# battery_current_sensor.net
KiCad netlist of a schematic drawn in Altium Designer
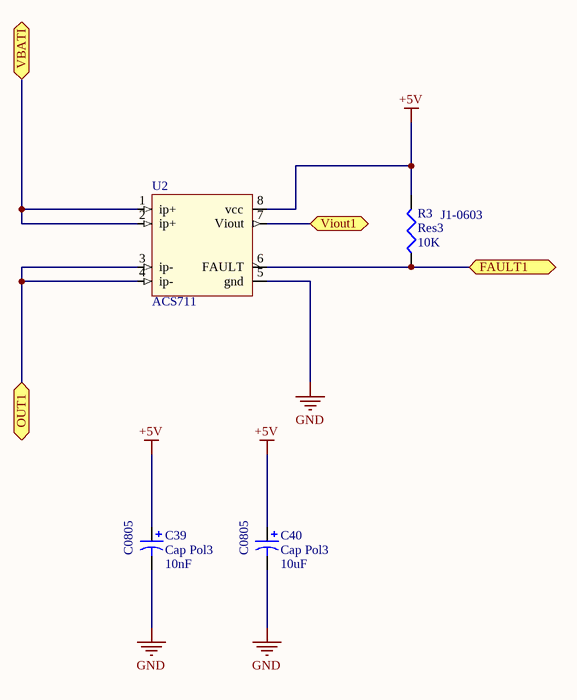
[diagram p0: battery current sensor.SchDoc]

(export (version "E")
  (design (tool "Eeschema 10.0.6"))
  (components
    (comp (ref "C39")
      (value "Cap Pol3")
      (footprint "C0805")
      (description "Polarized Capacitor (Surface Mount)")
      (fields
        (field (name "PACKAGEREFERENCE") "C0805")
        (field (name "ALTIUM_VALUE") "10nF")
        (field (name "PUBLISHER") "Altium Limited")
      )
      (libsource (lib "Miscellaneous Devices") (part "Cap Pol3"))
    )
    (comp (ref "C40")
      (value "Cap Pol3")
      (footprint "C0805")
      (description "Polarized Capacitor (Surface Mount)")
      (fields
        (field (name "PACKAGEREFERENCE") "C0805")
        (field (name "ALTIUM_VALUE") "10uF")
        (field (name "PUBLISHER") "Altium Limited")
      )
      (libsource (lib "Miscellaneous Devices") (part "Cap Pol3"))
    )
    (comp (ref "R3")
      (value "Res3")
      (footprint "J1-0603")
      (description "Resistor")
      (fields
        (field (name "PACKAGEREFERENCE") "J1-0603")
        (field (name "ALTIUM_VALUE") "10K")
        (field (name "PUBLISHER") "Altium Limited")
      )
      (libsource (lib "Miscellaneous Devices") (part "Res3"))
    )
    (comp (ref "U2") (value "ACS711") (footprint "ACS711") (libsource (lib "ACS711") (part "ACS711")))
  )
  (nets
    (net (code "1") (name "+5V") (class "Default")
      (node (ref "C39") (pin "1") (pinfunction "1_1") (pintype "passive"))
      (node (ref "C40") (pin "1") (pinfunction "1_1") (pintype "passive"))
      (node (ref "R3") (pin "2") (pinfunction "2_2") (pintype "passive"))
      (node (ref "U2") (pin "8") (pinfunction "vcc_8") (pintype "passive"))
    )
    (net (code "2") (name "/FAULT1") (class "Default")
      (node (ref "R3") (pin "1") (pinfunction "1_1") (pintype "passive"))
      (node (ref "U2") (pin "6") (pinfunction "FAULT_6") (pintype "open_collector"))
    )
    (net (code "3") (name "/OUT1") (class "Default")
      (node (ref "U2") (pin "3") (pinfunction "ip-_3") (pintype "input"))
      (node (ref "U2") (pin "4") (pinfunction "ip-_4") (pintype "input"))
    )
    (net (code "4") (name "/VBATI") (class "Default")
      (node (ref "U2") (pin "1") (pinfunction "ip+_1") (pintype "input"))
      (node (ref "U2") (pin "2") (pinfunction "ip+_2") (pintype "input"))
    )
    (net (code "5") (name "/Viout1") (class "Default")
      (node (ref "U2") (pin "7") (pinfunction "Viout_7") (pintype "output"))
    )
    (net (code "6") (name "GND") (class "Default")
      (node (ref "C39") (pin "2") (pinfunction "2_2") (pintype "passive"))
      (node (ref "C40") (pin "2") (pinfunction "2_2") (pintype "passive"))
      (node (ref "U2") (pin "5") (pinfunction "gnd_5") (pintype "passive"))
    )
  )
)
